# B4L_power_PCB.net
KiCad netlist of a schematic drawn in EAGLE
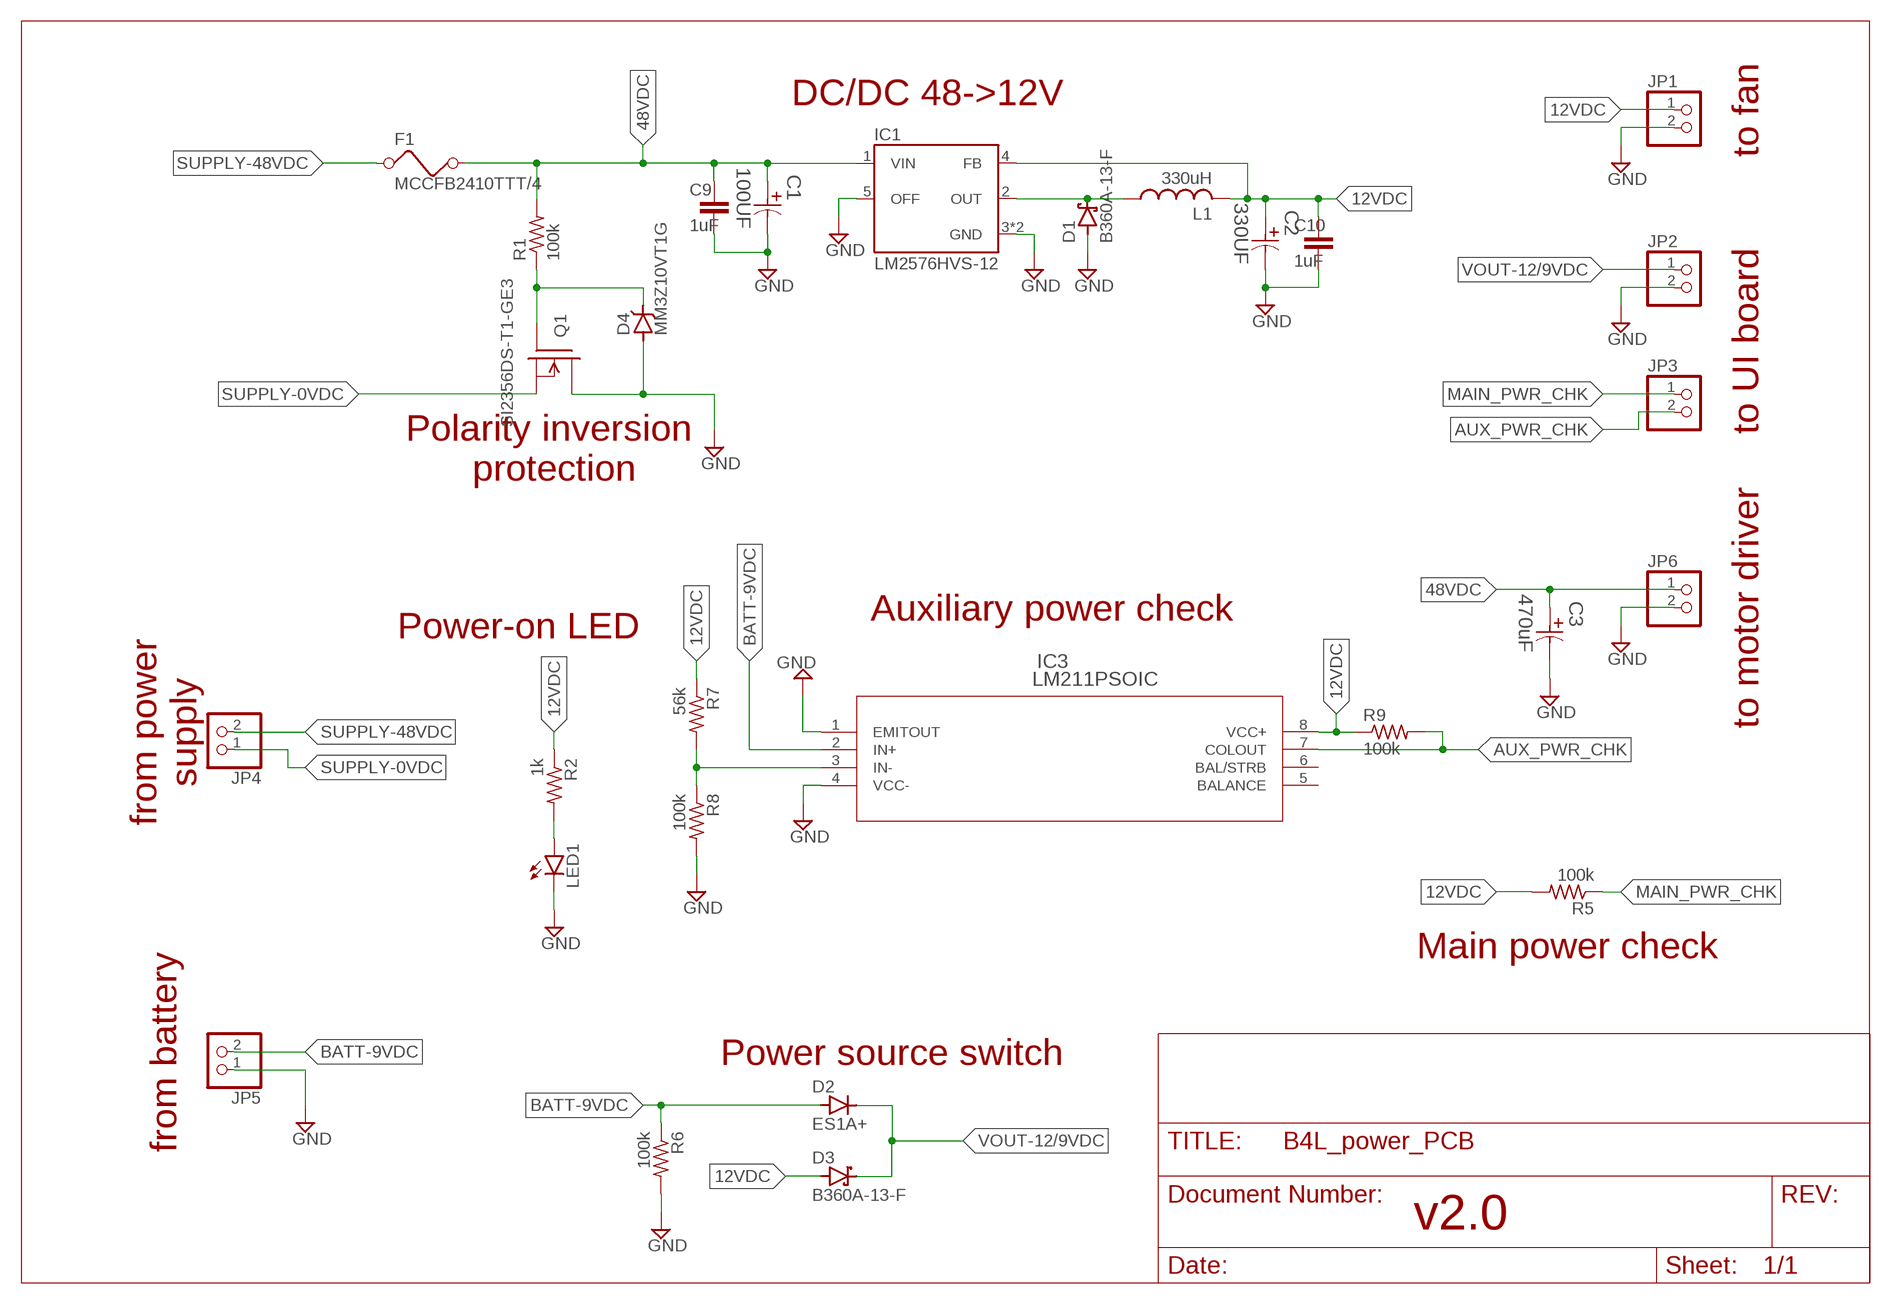
[diagram p0: schematic, sheet 1]

(export (version "E")
  (design (tool "Eeschema 10.0.6"))
  (components
    (comp (ref "C1")
      (value "100UF")
      (footprint "eagle-import:CAPAE1900X2200N")
      (fields (field (name "MPN") "EEV-EB2D101M") (field (name "TOLERANCE") "±20 %"))
      (libsource (lib "eagle-import") (part "EEV--CASE-K21EB2D101M"))
    )
    (comp (ref "C2")
      (value "330UF")
      (footprint "eagle-import:CAPAE830X1050N")
      (fields (field (name "MPN") "EEE-FT1V331AP") (field (name "TOLERANCE") "±20 %"))
      (libsource (lib "eagle-import") (part "EEE--CASE-FFT1V331AP"))
    )
    (comp (ref "C3")
      (value "470uF")
      (footprint "eagle-import:CAPAE1900X1700N")
      (libsource (lib "eagle-import") (part "EEVFK1K471M-CASE-K16"))
    )
    (comp (ref "C9")
      (value "1uF")
      (footprint "eagle-import:C1206")
      (libsource (lib "eagle-import") (part "C-EUC1206"))
    )
    (comp (ref "C10")
      (value "1uF")
      (footprint "eagle-import:C0603")
      (libsource (lib "eagle-import") (part "C-EUC0603"))
    )
    (comp (ref "D1")
      (value "B360A-13-F")
      (footprint "eagle-import:DO214AC")
      (libsource (lib "eagle-import") (part "B360A-13-F"))
    )
    (comp (ref "D2")
      (value "ES1A+")
      (footprint "eagle-import:DO214AC")
      (libsource (lib "eagle-import") (part "ESIA+"))
    )
    (comp (ref "D3")
      (value "B360A-13-F")
      (footprint "eagle-import:DO214AC")
      (libsource (lib "eagle-import") (part "B360A-13-F"))
    )
    (comp (ref "D4")
      (value "MM3Z10VT1G")
      (footprint "eagle-import:SOD323")
      (libsource (lib "eagle-import") (part "MM3Z10VT1G"))
    )
    (comp (ref "F1")
      (value "MCCFB2410TTT/4")
      (footprint "eagle-import:MCCFB2410TTT_4")
      (libsource (lib "eagle-import") (part "MCCFB2410TTT/4"))
    )
    (comp (ref "IC1")
      (value "LM2576HVS-12")
      (footprint "eagle-import:TO263-5")
      (libsource (lib "eagle-import") (part "LM2576HVS"))
    )
    (comp (ref "IC3")
      (value "LM211PSOIC")
      (footprint "eagle-import:SO08")
      (libsource (lib "eagle-import") (part "LM211PSOIC"))
    )
    (comp (ref "JP1")
      (value "PINHD-1X2")
      (footprint "eagle-import:1X02")
      (libsource (lib "eagle-import") (part "PINHD-1X2"))
    )
    (comp (ref "JP2")
      (value "PINHD-1X2")
      (footprint "eagle-import:1X02")
      (libsource (lib "eagle-import") (part "PINHD-1X2"))
    )
    (comp (ref "JP3")
      (value "PINHD-1X2")
      (footprint "eagle-import:1X02")
      (libsource (lib "eagle-import") (part "PINHD-1X2"))
    )
    (comp (ref "JP4")
      (value "PINHD-1X2")
      (footprint "eagle-import:1X02")
      (libsource (lib "eagle-import") (part "PINHD-1X2"))
    )
    (comp (ref "JP5")
      (value "PINHD-1X2")
      (footprint "eagle-import:1X02")
      (libsource (lib "eagle-import") (part "PINHD-1X2"))
    )
    (comp (ref "JP6")
      (value "PINHD-1X2")
      (footprint "eagle-import:1X02")
      (libsource (lib "eagle-import") (part "PINHD-1X2"))
    )
    (comp (ref "L1")
      (value "330uH")
      (footprint "eagle-import:SRR1280A-331K")
      (libsource (lib "eagle-import") (part "SRR1280A-331K"))
    )
    (comp (ref "LED1")
      (value "LED3MM")
      (footprint "eagle-import:LED3MM")
      (libsource (lib "eagle-import") (part "LED3MM"))
    )
    (comp (ref "Q1")
      (value "SI2356DS-T1-GE3")
      (footprint "eagle-import:SOT23")
      (libsource (lib "eagle-import") (part "SI2356DS-T1-GE3"))
    )
    (comp (ref "R1")
      (value "100k")
      (footprint "eagle-import:R0603")
      (libsource (lib "eagle-import") (part "R-US_R0603"))
    )
    (comp (ref "R2")
      (value "1k")
      (footprint "eagle-import:R0603")
      (libsource (lib "eagle-import") (part "R-US_R0603"))
    )
    (comp (ref "R5")
      (value "100k")
      (footprint "eagle-import:R0603")
      (libsource (lib "eagle-import") (part "R-US_R0603"))
    )
    (comp (ref "R6")
      (value "100k")
      (footprint "eagle-import:R0603")
      (libsource (lib "eagle-import") (part "R-US_R0603"))
    )
    (comp (ref "R7")
      (value "56k")
      (footprint "eagle-import:R0603")
      (libsource (lib "eagle-import") (part "R-US_R0603"))
    )
    (comp (ref "R8")
      (value "100k")
      (footprint "eagle-import:R0603")
      (libsource (lib "eagle-import") (part "R-US_R0603"))
    )
    (comp (ref "R9")
      (value "100k")
      (footprint "eagle-import:R0603")
      (libsource (lib "eagle-import") (part "R-US_R0603"))
    )
  )
  (nets
    (net (code "1") (name "12VDC") (class "Default")
      (node (ref "C10") (pin "1") (pinfunction "1_1") (pintype "passive"))
      (node (ref "C2") (pin "1") (pinfunction "1_1") (pintype "passive"))
      (node (ref "D3") (pin "A") (pinfunction "A_A") (pintype "passive"))
      (node (ref "IC1") (pin "4") (pinfunction "FB_4") (pintype "input"))
      (node (ref "IC3") (pin "8") (pinfunction "VCC+_8") (pintype "power_in"))
      (node (ref "JP1") (pin "1") (pinfunction "1_1") (pintype "passive"))
      (node (ref "L1") (pin "P$2") (pinfunction "2_P$2") (pintype "passive"))
      (node (ref "R2") (pin "1") (pinfunction "1_1") (pintype "passive"))
      (node (ref "R5") (pin "2") (pinfunction "2_2") (pintype "passive"))
      (node (ref "R7") (pin "1") (pinfunction "1_1") (pintype "passive"))
      (node (ref "R9") (pin "1") (pinfunction "1_1") (pintype "passive"))
    )
    (net (code "2") (name "48VDC") (class "Default")
      (node (ref "C1") (pin "1") (pinfunction "1_1") (pintype "passive"))
      (node (ref "C3") (pin "1") (pinfunction "1_1") (pintype "passive"))
      (node (ref "C9") (pin "1") (pinfunction "1_1") (pintype "passive"))
      (node (ref "F1") (pin "P$2") (pinfunction "2_P$2") (pintype "passive"))
      (node (ref "IC1") (pin "1") (pinfunction "VIN_1") (pintype "power_in"))
      (node (ref "JP6") (pin "1") (pinfunction "1_1") (pintype "passive"))
      (node (ref "R1") (pin "2") (pinfunction "2_2") (pintype "passive"))
    )
    (net (code "3") (name "AUX_PWR_CHK") (class "Default")
      (node (ref "IC3") (pin "7") (pinfunction "COLOUT_7") (pintype "output"))
      (node (ref "JP3") (pin "2") (pinfunction "2_2") (pintype "passive"))
      (node (ref "R9") (pin "2") (pinfunction "2_2") (pintype "passive"))
    )
    (net (code "4") (name "BATT-9VDC") (class "Default")
      (node (ref "D2") (pin "A") (pinfunction "A_A") (pintype "passive"))
      (node (ref "IC3") (pin "2") (pinfunction "IN+_2") (pintype "input"))
      (node (ref "JP5") (pin "2") (pinfunction "2_2") (pintype "passive"))
      (node (ref "R6") (pin "1") (pinfunction "1_1") (pintype "passive"))
    )
    (net (code "5") (name "GND") (class "Default")
      (node (ref "C1") (pin "2") (pinfunction "2_2") (pintype "passive"))
      (node (ref "C10") (pin "2") (pinfunction "2_2") (pintype "passive"))
      (node (ref "C2") (pin "2") (pinfunction "2_2") (pintype "passive"))
      (node (ref "C3") (pin "2") (pinfunction "2_2") (pintype "passive"))
      (node (ref "C9") (pin "2") (pinfunction "2_2") (pintype "passive"))
      (node (ref "D1") (pin "A") (pinfunction "A_A") (pintype "passive"))
      (node (ref "D4") (pin "2") (pinfunction "A_2") (pintype "passive"))
      (node (ref "IC1") (pin "3") (pinfunction "GND_3") (pintype "power_in"))
      (node (ref "IC1") (pin "5") (pinfunction "OFF_5") (pintype "input"))
      (node (ref "IC1") (pin "6") (pinfunction "GND_6") (pintype "power_in"))
      (node (ref "IC3") (pin "1") (pinfunction "EMITOUT_1") (pintype "output"))
      (node (ref "IC3") (pin "4") (pinfunction "VCC-_4") (pintype "power_in"))
      (node (ref "JP1") (pin "2") (pinfunction "2_2") (pintype "passive"))
      (node (ref "JP2") (pin "2") (pinfunction "2_2") (pintype "passive"))
      (node (ref "JP5") (pin "1") (pinfunction "1_1") (pintype "passive"))
      (node (ref "JP6") (pin "2") (pinfunction "2_2") (pintype "passive"))
      (node (ref "LED1") (pin "K") (pinfunction "C_K") (pintype "passive"))
      (node (ref "Q1") (pin "3") (pinfunction "D_3") (pintype "passive"))
      (node (ref "R6") (pin "2") (pinfunction "2_2") (pintype "passive"))
      (node (ref "R8") (pin "2") (pinfunction "2_2") (pintype "passive"))
    )
    (net (code "6") (name "MAIN_PWR_CHK") (class "Default")
      (node (ref "JP3") (pin "1") (pinfunction "1_1") (pintype "passive"))
      (node (ref "R5") (pin "1") (pinfunction "1_1") (pintype "passive"))
    )
    (net (code "7") (name "Net-(D4-C)") (class "Default")
      (node (ref "D4") (pin "1") (pinfunction "C_1") (pintype "passive"))
      (node (ref "Q1") (pin "1") (pinfunction "G_1") (pintype "passive"))
      (node (ref "R1") (pin "1") (pinfunction "1_1") (pintype "passive"))
    )
    (net (code "8") (name "Net-(IC1-OUT)") (class "Default")
      (node (ref "D1") (pin "C") (pinfunction "C_C") (pintype "passive"))
      (node (ref "IC1") (pin "2") (pinfunction "OUT_2") (pintype "output"))
      (node (ref "L1") (pin "P$1") (pinfunction "1_P$1") (pintype "passive"))
    )
    (net (code "9") (name "Net-(IC3-IN-)") (class "Default")
      (node (ref "IC3") (pin "3") (pinfunction "IN-_3") (pintype "input"))
      (node (ref "R7") (pin "2") (pinfunction "2_2") (pintype "passive"))
      (node (ref "R8") (pin "1") (pinfunction "1_1") (pintype "passive"))
    )
    (net (code "10") (name "Net-(LED1-PadA)") (class "Default")
      (node (ref "LED1") (pin "A") (pinfunction "A_A") (pintype "passive"))
      (node (ref "R2") (pin "2") (pinfunction "2_2") (pintype "passive"))
    )
    (net (code "11") (name "SUPPLY-0VDC") (class "Default")
      (node (ref "JP4") (pin "1") (pinfunction "1_1") (pintype "passive"))
      (node (ref "Q1") (pin "2") (pinfunction "S_2") (pintype "passive"))
    )
    (net (code "12") (name "SUPPLY-48VDC") (class "Default")
      (node (ref "F1") (pin "P$1") (pinfunction "1_P$1") (pintype "passive"))
      (node (ref "JP4") (pin "2") (pinfunction "2_2") (pintype "passive"))
    )
    (net (code "13") (name "VOUT-12{slash}9VDC") (class "Default")
      (node (ref "D2") (pin "C") (pinfunction "C_C") (pintype "passive"))
      (node (ref "D3") (pin "C") (pinfunction "C_C") (pintype "passive"))
      (node (ref "JP2") (pin "1") (pinfunction "1_1") (pintype "passive"))
    )
    (net (code "14") (name "unconnected-(IC3-BALANCE-Pad5)") (class "Default")
      (node (ref "IC3") (pin "5") (pinfunction "BALANCE_5") (pintype "passive"))
    )
    (net (code "15") (name "unconnected-(IC3-BAL{slash}STRB-Pad6)") (class "Default")
      (node (ref "IC3") (pin "6") (pinfunction "BAL/STRB_6") (pintype "passive"))
    )
  )
)
